# sheet1_mcu_radio.net
KiCad netlist of a schematic drawn in Altium Designer
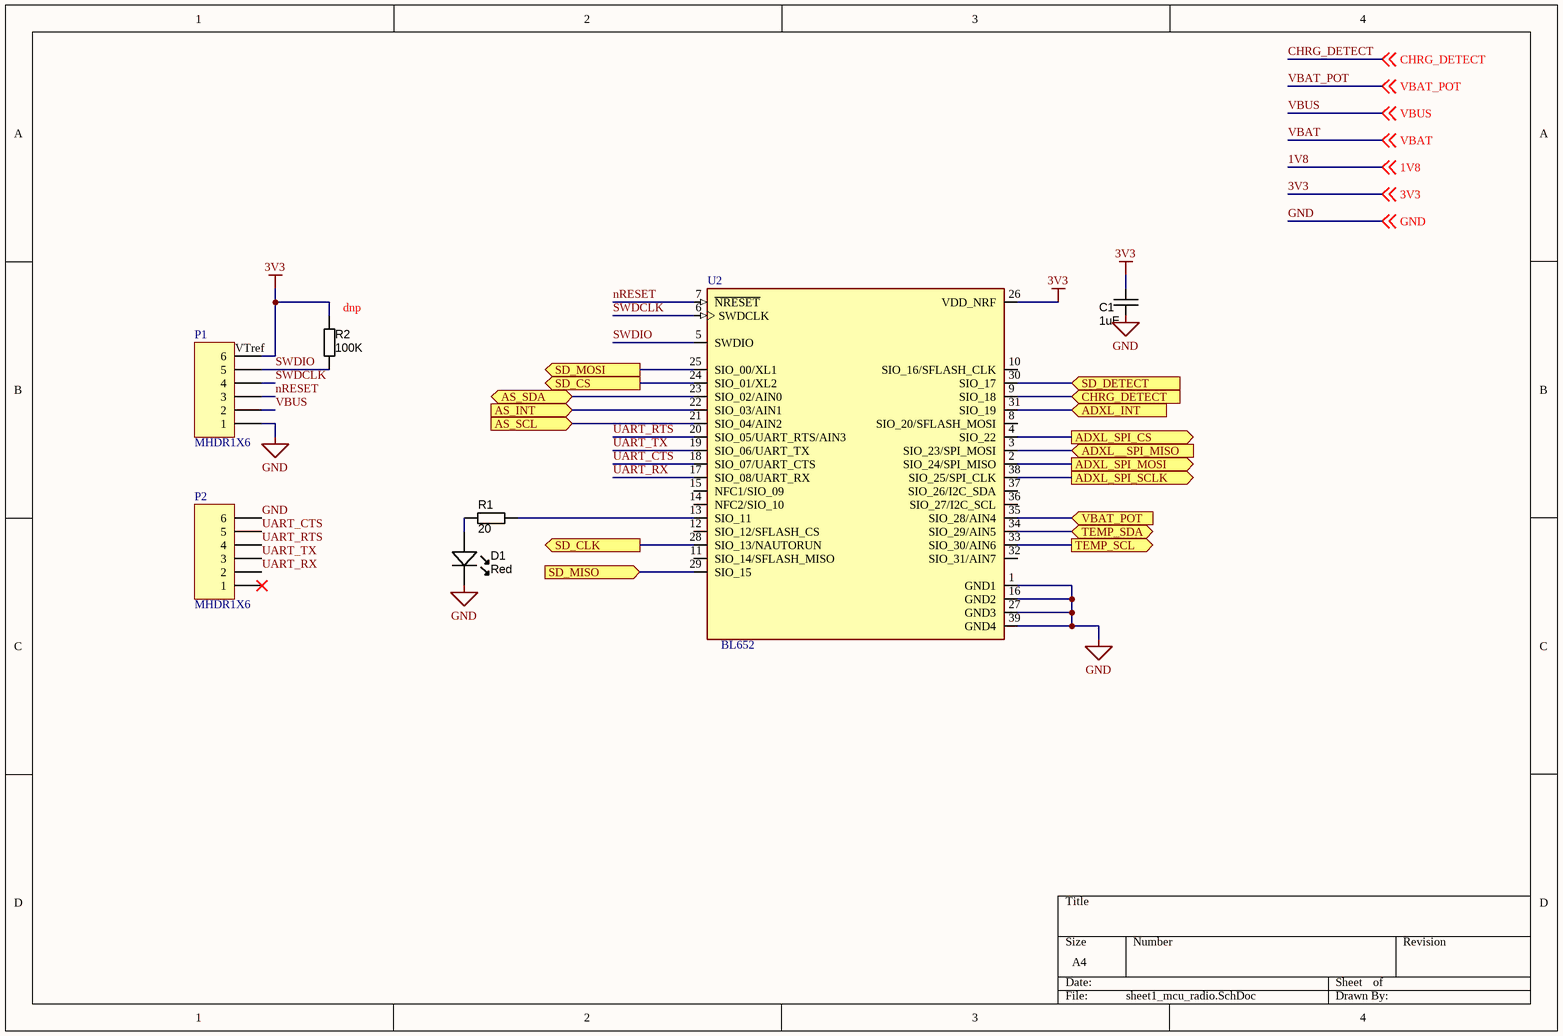
[diagram p0: sheet1_mcu_radio.SchDoc]

(export (version "E")
  (design (tool "Eeschema 10.0.6"))
  (components
    (comp (ref "C1")
      (value "1uF")
      (footprint "CAPC1608X90N")
      (description "Capacitor SMD Cer 10uF 10% 16V X5R 0603")
      (fields (field (name "TOLERANCE") "±10%") (field (name "MANUFACTURER") "TDK"))
      (libsource (lib "UEKAE") (part "CAPC_100n_0603_X7R_50V_10%"))
    )
    (comp (ref "D1")
      (value "Red")
      (footprint "LED-0603-RED")
      (description "Dialight 598-8E40-107F")
      (libsource (lib "Libs_RRutledge") (part "LED_SMD_Red_0603_220mcd"))
    )
    (comp (ref "P1")
      (value "MHDR1X6")
      (footprint "MHDR1X6")
      (description "Header, 6-Pin")
      (fields (field (name "PUBLISHER") "Altium Limited"))
      (libsource (lib "Miscellaneous Connectors") (part "MHDR1X6"))
    )
    (comp (ref "P2")
      (value "MHDR1X6")
      (footprint "MHDR1X6")
      (description "Header, 6-Pin")
      (fields (field (name "PUBLISHER") "Altium Limited"))
      (libsource (lib "Miscellaneous Connectors") (part "MHDR1X6"))
    )
    (comp (ref "R1")
      (value "20")
      (footprint "RESC1005X40N")
      (description "Resistor SMD chip 100k Ohm 0.063W 5% 0402")
      (fields (field (name "TOLERANCE") "±5%") (field (name "Comment") "Thick Film"))
      (libsource (lib "") (part "RES_100K_0402_5%_1"))
    )
    (comp (ref "R2")
      (value "100K")
      (footprint "RESC1005X40N")
      (description "Resistor SMD chip 100k Ohm 0.063W 5% 0402")
      (fields (field (name "TOLERANCE") "±5%") (field (name "Comment") "Thick Film"))
      (libsource (lib "Libs_RRutledge") (part "RES_100K_0402_5%"))
    )
    (comp (ref "U2")
      (value "BL652")
      (footprint "BL652")
      (libsource (lib "Light Sensor Prototype") (part "BL652"))
    )
  )
  (nets
    (net (code "1") (name "/ADXL_INT") (class "Default")
      (node (ref "U2") (pin "31") (pinfunction "SIO_19_31") (pintype "bidirectional"))
    )
    (net (code "2") (name "/ADXL_SPI_CS") (class "Default")
      (node (ref "U2") (pin "4") (pinfunction "SIO_22_4") (pintype "bidirectional"))
    )
    (net (code "3") (name "/ADXL_SPI_MOSI") (class "Default")
      (node (ref "U2") (pin "2") (pinfunction "SIO_24/SPI_MISO_2") (pintype "bidirectional"))
    )
    (net (code "4") (name "/ADXL_SPI_SCLK") (class "Default")
      (node (ref "U2") (pin "38") (pinfunction "SIO_25/SPI_CLK_38") (pintype "bidirectional"))
    )
    (net (code "5") (name "/ADXL__SPI_MISO") (class "Default")
      (node (ref "U2") (pin "3") (pinfunction "SIO_23/SPI_MOSI_3") (pintype "bidirectional"))
    )
    (net (code "6") (name "/AS_INT") (class "Default")
      (node (ref "U2") (pin "22") (pinfunction "SIO_03/AIN1_22") (pintype "bidirectional"))
    )
    (net (code "7") (name "/AS_SCL") (class "Default")
      (node (ref "U2") (pin "21") (pinfunction "SIO_04/AIN2_21") (pintype "bidirectional"))
    )
    (net (code "8") (name "/AS_SDA") (class "Default")
      (node (ref "U2") (pin "23") (pinfunction "SIO_02/AIN0_23") (pintype "bidirectional"))
    )
    (net (code "9") (name "/SD_CLK") (class "Default")
      (node (ref "U2") (pin "28") (pinfunction "SIO_13/NAUTORUN_28") (pintype "bidirectional"))
    )
    (net (code "10") (name "/SD_CS") (class "Default")
      (node (ref "U2") (pin "24") (pinfunction "SIO_01/XL2_24") (pintype "bidirectional"))
    )
    (net (code "11") (name "/SD_DETECT") (class "Default")
      (node (ref "U2") (pin "30") (pinfunction "SIO_17_30") (pintype "bidirectional"))
    )
    (net (code "12") (name "/SD_MISO") (class "Default")
      (node (ref "U2") (pin "29") (pinfunction "SIO_15_29") (pintype "bidirectional"))
    )
    (net (code "13") (name "/SD_MOSI") (class "Default")
      (node (ref "U2") (pin "25") (pinfunction "SIO_00/XL1_25") (pintype "bidirectional"))
    )
    (net (code "14") (name "/SWDCLK") (class "Default")
      (node (ref "P1") (pin "4") (pinfunction "4_4") (pintype "passive"))
      (node (ref "U2") (pin "6") (pinfunction "SWDCLK_6") (pintype "input"))
    )
    (net (code "15") (name "/SWDIO") (class "Default")
      (node (ref "P1") (pin "5") (pinfunction "5_5") (pintype "passive"))
      (node (ref "R2") (pin "2") (pinfunction "2_2") (pintype "passive"))
      (node (ref "U2") (pin "5") (pinfunction "SWDIO_5") (pintype "bidirectional"))
    )
    (net (code "16") (name "/TEMP_SCL") (class "Default")
      (node (ref "U2") (pin "33") (pinfunction "SIO_30/AIN6_33") (pintype "bidirectional"))
    )
    (net (code "17") (name "/TEMP_SDA") (class "Default")
      (node (ref "U2") (pin "34") (pinfunction "SIO_29/AIN5_34") (pintype "bidirectional"))
    )
    (net (code "18") (name "/UART_CTS") (class "Default")
      (node (ref "P2") (pin "5") (pinfunction "5_5") (pintype "passive"))
      (node (ref "U2") (pin "18") (pinfunction "SIO_07/UART_CTS_18") (pintype "bidirectional"))
    )
    (net (code "19") (name "/UART_RTS") (class "Default")
      (node (ref "P2") (pin "4") (pinfunction "4_4") (pintype "passive"))
      (node (ref "U2") (pin "20") (pinfunction "SIO_05/UART_RTS/AIN3_20") (pintype "bidirectional"))
    )
    (net (code "20") (name "/UART_RX") (class "Default")
      (node (ref "P2") (pin "2") (pinfunction "2_2") (pintype "passive"))
      (node (ref "U2") (pin "17") (pinfunction "SIO_08/UART_RX_17") (pintype "bidirectional"))
    )
    (net (code "21") (name "/UART_TX") (class "Default")
      (node (ref "P2") (pin "3") (pinfunction "3_3") (pintype "passive"))
      (node (ref "U2") (pin "19") (pinfunction "SIO_06/UART_TX_19") (pintype "bidirectional"))
    )
    (net (code "22") (name "/nRESET") (class "Default")
      (node (ref "P1") (pin "3") (pinfunction "3_3") (pintype "passive"))
      (node (ref "U2") (pin "7") (pinfunction "~{NRESET}_7") (pintype "input"))
    )
    (net (code "24") (name "3V3") (class "Default")
      (node (ref "C1") (pin "1") (pintype "passive"))
      (node (ref "P1") (pin "6") (pinfunction "6_6") (pintype "passive"))
      (node (ref "R2") (pin "1") (pinfunction "1_1") (pintype "passive"))
      (node (ref "U2") (pin "26") (pinfunction "VDD_NRF_26") (pintype "power_in"))
    )
    (net (code "25") (name "CHRG_DETECT") (class "Default")
      (node (ref "U2") (pin "9") (pinfunction "SIO_18_9") (pintype "bidirectional"))
    )
    (net (code "26") (name "GND") (class "Default")
      (node (ref "C1") (pin "2") (pintype "passive"))
      (node (ref "D1") (pin "K") (pinfunction "K_K") (pintype "passive"))
      (node (ref "P1") (pin "1") (pinfunction "1_1") (pintype "passive"))
      (node (ref "P2") (pin "6") (pinfunction "6_6") (pintype "passive"))
      (node (ref "U2") (pin "1") (pinfunction "GND1_1") (pintype "power_in"))
      (node (ref "U2") (pin "16") (pinfunction "GND2_16") (pintype "power_in"))
      (node (ref "U2") (pin "27") (pinfunction "GND3_27") (pintype "power_in"))
      (node (ref "U2") (pin "39") (pinfunction "GND4_39") (pintype "power_in"))
    )
    (net (code "27") (name "Net-(D1-PadA)") (class "Default")
      (node (ref "D1") (pin "A") (pinfunction "A_A") (pintype "passive"))
      (node (ref "R1") (pin "1") (pinfunction "1_1") (pintype "passive"))
    )
    (net (code "28") (name "Net-(U2-SIO_11)") (class "Default")
      (node (ref "R1") (pin "2") (pinfunction "2_2") (pintype "passive"))
      (node (ref "U2") (pin "13") (pinfunction "SIO_11_13") (pintype "bidirectional"))
    )
    (net (code "30") (name "VBAT_POT") (class "Default")
      (node (ref "U2") (pin "35") (pinfunction "SIO_28/AIN4_35") (pintype "bidirectional"))
    )
    (net (code "31") (name "VBUS") (class "Default")
      (node (ref "P1") (pin "2") (pinfunction "2_2") (pintype "passive"))
    )
    (net (code "32") (name "unconnected-(P2-Pad1)") (class "Default")
      (node (ref "P2") (pin "1") (pinfunction "1_1") (pintype "passive+no_connect"))
    )
    (net (code "33") (name "unconnected-(U2-NFC1{slash}SIO_09-Pad15)") (class "Default")
      (node (ref "U2") (pin "15") (pinfunction "NFC1/SIO_09_15") (pintype "bidirectional"))
    )
    (net (code "34") (name "unconnected-(U2-NFC2{slash}SIO_10-Pad14)") (class "Default")
      (node (ref "U2") (pin "14") (pinfunction "NFC2/SIO_10_14") (pintype "bidirectional"))
    )
    (net (code "35") (name "unconnected-(U2-SIO_12{slash}SFLASH_CS-Pad12)") (class "Default")
      (node (ref "U2") (pin "12") (pinfunction "SIO_12/SFLASH_CS_12") (pintype "bidirectional"))
    )
    (net (code "36") (name "unconnected-(U2-SIO_14{slash}SFLASH_MISO-Pad11)") (class "Default")
      (node (ref "U2") (pin "11") (pinfunction "SIO_14/SFLASH_MISO_11") (pintype "bidirectional"))
    )
    (net (code "37") (name "unconnected-(U2-SIO_16{slash}SFLASH_CLK-Pad10)") (class "Default")
      (node (ref "U2") (pin "10") (pinfunction "SIO_16/SFLASH_CLK_10") (pintype "bidirectional"))
    )
    (net (code "38") (name "unconnected-(U2-SIO_20{slash}SFLASH_MOSI-Pad8)") (class "Default")
      (node (ref "U2") (pin "8") (pinfunction "SIO_20/SFLASH_MOSI_8") (pintype "bidirectional"))
    )
    (net (code "39") (name "unconnected-(U2-SIO_26{slash}I2C_SDA-Pad37)") (class "Default")
      (node (ref "U2") (pin "37") (pinfunction "SIO_26/I2C_SDA_37") (pintype "bidirectional"))
    )
    (net (code "40") (name "unconnected-(U2-SIO_27{slash}I2C_SCL-Pad36)") (class "Default")
      (node (ref "U2") (pin "36") (pinfunction "SIO_27/I2C_SCL_36") (pintype "bidirectional"))
    )
    (net (code "41") (name "unconnected-(U2-SIO_31{slash}AIN7-Pad32)") (class "Default")
      (node (ref "U2") (pin "32") (pinfunction "SIO_31/AIN7_32") (pintype "bidirectional"))
    )
  )
)
